# Buck_CurrentRegulator.net
KiCad netlist of a schematic drawn in Altium Designer
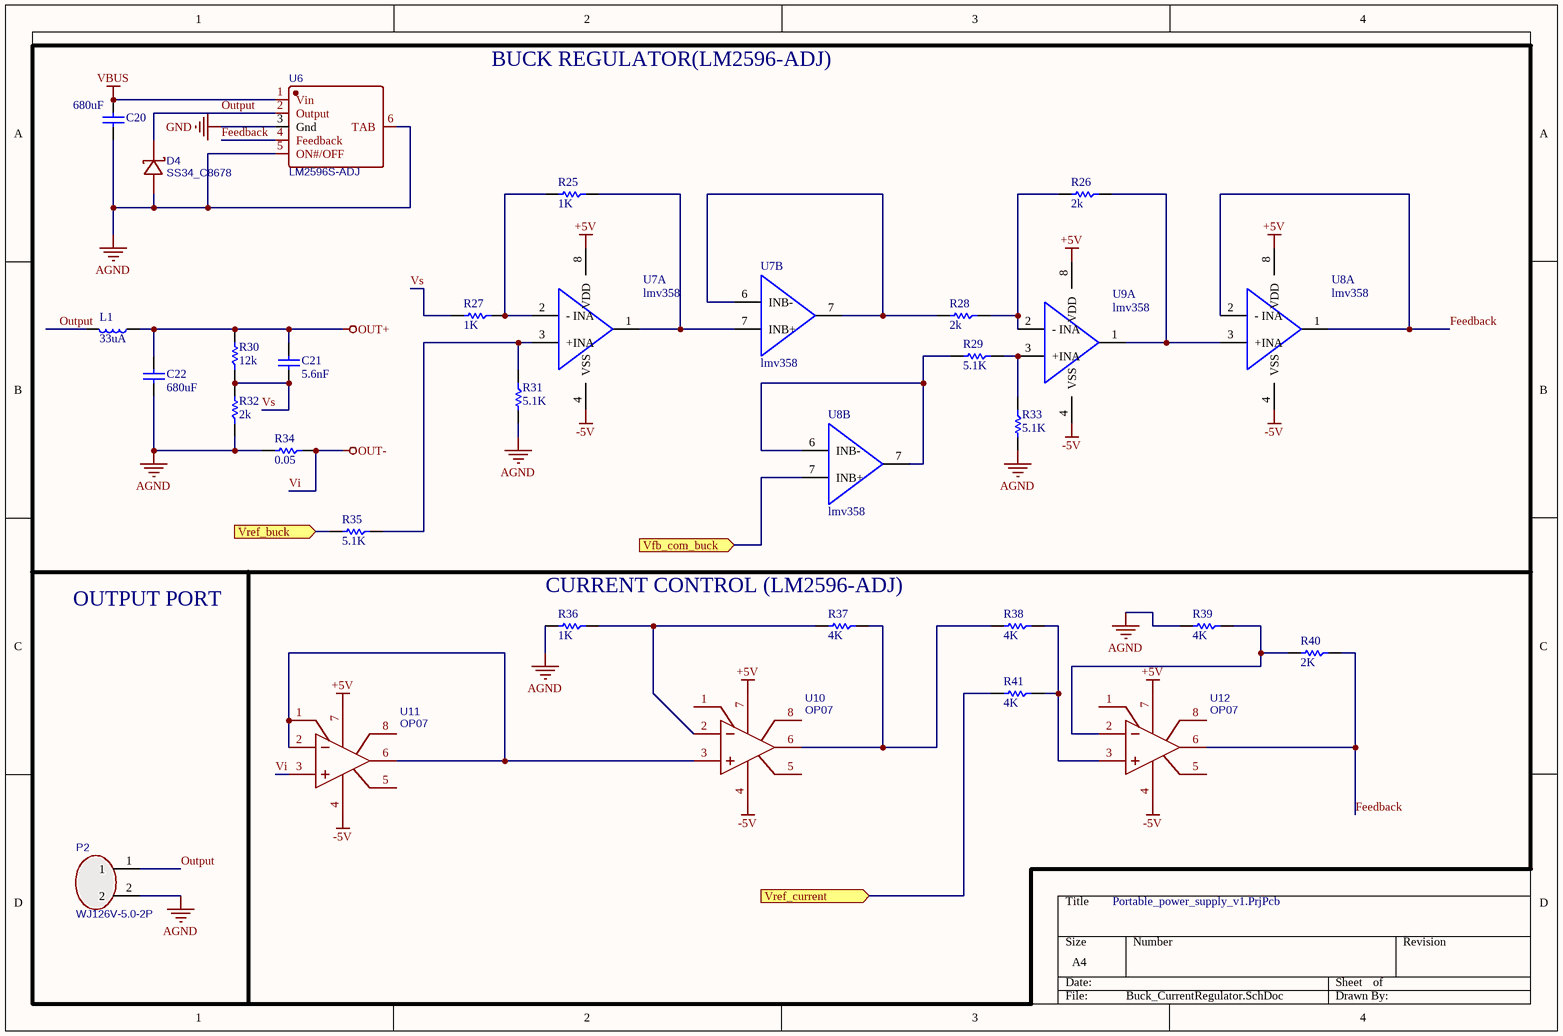
[diagram p0: Buck_CurrentRegulator.SchDoc]

(export (version "E")
  (design (tool "Eeschema 10.0.6"))
  (components
    (comp (ref "C20")
      (value "680uF")
      (footprint "0805C")
      (description "Capacitor")
      (fields (field (name "REVIEWED BY") "RM - 2018/08/05"))
      (libsource (lib "Portable power supply") (part "C_680uf"))
    )
    (comp (ref "C21")
      (value "5.6nF")
      (footprint "0805C")
      (description "Capacitor")
      (fields (field (name "REVIEWED BY") "RM - 2018/08/05"))
      (libsource (lib "Portable power supply") (part "C_7"))
    )
    (comp (ref "C22")
      (value "680uF")
      (footprint "0805C")
      (description "Capacitor")
      (fields (field (name "REVIEWED BY") "RM - 2018/08/05"))
      (libsource (lib "Portable power supply") (part "C_11"))
    )
    (comp (ref "D4")
      (value "SS34_C8678")
      (footprint "DO-214AC_L4.3-W2.7-LS5.3-RD")
      (fields (field (name "BOM_MANUFACTURER PART") "SS34") (field (name "BOM_SUPPLIER PART") "C8678"))
      (libsource (lib "Portable power supply") (part "SS34_C8678"))
    )
    (comp (ref "L1")
      (value "33uA")
      (footprint "0805")
      (description "Inductor")
      (fields (field (name "REVIEWED BY") "RM - 2018/08/05"))
      (libsource (lib "Portable power supply") (part "I"))
    )
    (comp (ref "P2")
      (value "WJ126V-5.0-2P")
      (footprint "CONN-TH_WJ126V-5.0-2P")
      (fields (field (name "BOM_SUPPLIER PART") "C8404"))
      (libsource (lib "Portable power supply") (part "WJ126V-5.0-2P"))
    )
    (comp (ref "R25")
      (value "1K")
      (footprint "0805")
      (description "Resistor")
      (fields (field (name "REVIEWED BY") "RM - 2018/08/05"))
      (libsource (lib "Portable power supply") (part "R_6"))
    )
    (comp (ref "R26")
      (value "2k")
      (footprint "0805")
      (description "Resistor")
      (fields (field (name "REVIEWED BY") "RM - 2018/08/05"))
      (libsource (lib "Portable power supply") (part "R_3"))
    )
    (comp (ref "R27")
      (value "1K")
      (footprint "0805")
      (description "Resistor")
      (fields (field (name "REVIEWED BY") "RM - 2018/08/05"))
      (libsource (lib "Portable power supply") (part "R_6"))
    )
    (comp (ref "R28")
      (value "2k")
      (footprint "0805")
      (description "Resistor")
      (fields (field (name "REVIEWED BY") "RM - 2018/08/05"))
      (libsource (lib "Portable power supply") (part "R_3"))
    )
    (comp (ref "R29")
      (value "5.1K")
      (footprint "0805")
      (description "Resistor")
      (fields (field (name "REVIEWED BY") "RM - 2018/08/05"))
      (libsource (lib "Portable power supply") (part "R_1"))
    )
    (comp (ref "R30")
      (value "12k")
      (footprint "0805")
      (description "Resistor")
      (fields (field (name "REVIEWED BY") "RM - 2018/08/05"))
      (libsource (lib "Portable power supply") (part "R_2"))
    )
    (comp (ref "R31")
      (value "5.1K")
      (footprint "0805")
      (description "Resistor")
      (fields (field (name "REVIEWED BY") "RM - 2018/08/05"))
      (libsource (lib "Portable power supply") (part "R_1"))
    )
    (comp (ref "R32")
      (value "2k")
      (footprint "0805")
      (description "Resistor")
      (fields (field (name "REVIEWED BY") "RM - 2018/08/05"))
      (libsource (lib "Portable power supply") (part "R_3"))
    )
    (comp (ref "R33")
      (value "5.1K")
      (footprint "0805")
      (description "Resistor")
      (fields (field (name "REVIEWED BY") "RM - 2018/08/05"))
      (libsource (lib "Portable power supply") (part "R_1"))
    )
    (comp (ref "R34")
      (value "0.05")
      (footprint "0805")
      (description "Resistor")
      (fields (field (name "REVIEWED BY") "RM - 2018/08/05"))
      (libsource (lib "Portable power supply") (part "R_6"))
    )
    (comp (ref "R35")
      (value "5.1K")
      (footprint "0805")
      (description "Resistor")
      (fields (field (name "REVIEWED BY") "RM - 2018/08/05"))
      (libsource (lib "Portable power supply") (part "R_1"))
    )
    (comp (ref "R36")
      (value "1K")
      (footprint "0805")
      (description "Resistor")
      (fields (field (name "REVIEWED BY") "RM - 2018/08/05"))
      (libsource (lib "power supply ztc") (part "R_1k"))
    )
    (comp (ref "R37")
      (value "4K")
      (footprint "0805")
      (description "Resistor")
      (fields (field (name "REVIEWED BY") "RM - 2018/08/05"))
      (libsource (lib "power supply ztc") (part "R_1k"))
    )
    (comp (ref "R38")
      (value "4K")
      (footprint "0805")
      (description "Resistor")
      (fields (field (name "REVIEWED BY") "RM - 2018/08/05"))
      (libsource (lib "power supply ztc") (part "R_1k"))
    )
    (comp (ref "R39")
      (value "4K")
      (footprint "0805")
      (description "Resistor")
      (fields (field (name "REVIEWED BY") "RM - 2018/08/05"))
      (libsource (lib "power supply ztc") (part "R_1k"))
    )
    (comp (ref "R40")
      (value "2K")
      (footprint "0805")
      (description "Resistor")
      (fields (field (name "REVIEWED BY") "RM - 2018/08/05"))
      (libsource (lib "power supply ztc") (part "R_1k"))
    )
    (comp (ref "R41")
      (value "4K")
      (footprint "0805")
      (description "Resistor")
      (fields (field (name "REVIEWED BY") "RM - 2018/08/05"))
      (libsource (lib "power supply ztc") (part "R_1k"))
    )
    (comp (ref "U6")
      (value "LM2596S-ADJ")
      (footprint "TO-263-5_L10.2-W8.9-P1.70-BR")
      (fields (field (name "BOM_SUPPLIER PART") "C347423") (field (name "CONTRIBUTOR") "LCSC"))
      (libsource (lib "Portable power supply") (part "LM2596S-ADJ"))
    )
    (comp (ref "U7")
      (value "lmv358")
      (footprint "SOP-8_L4.9-W3.9-P1.27-LS6.0-BL")
      (description "OpAmp High Frequency Dual")
      (fields (field (name "REVIEWED BY") "RM - 2018/08/05"))
      (libsource (lib "Portable power supply") (part "LMV358-SR"))
    )
    (comp (ref "U8")
      (value "lmv358")
      (footprint "SOP-8_L4.9-W3.9-P1.27-LS6.0-BL")
      (description "OpAmp High Frequency Dual")
      (fields (field (name "REVIEWED BY") "RM - 2018/08/05"))
      (libsource (lib "Portable power supply") (part "LMV358-SR"))
    )
    (comp (ref "U9")
      (value "lmv358")
      (footprint "SOP-8_L4.9-W3.9-P1.27-LS6.0-BL")
      (description "OpAmp High Frequency Dual")
      (fields (field (name "REVIEWED BY") "RM - 2018/08/05"))
      (libsource (lib "Portable power supply") (part "LMV358-SR"))
    )
    (comp (ref "U10")
      (value "OP07")
      (footprint "op07:SOP-8_L4.9-W3.9-P1.27-LS6.0-BL")
      (fields (field (name "BOM_SUPPLIER PART") "C1508997") (field (name "CONTRIBUTOR") "LCSC"))
      (libsource (lib "op07") (part "OP07"))
    )
    (comp (ref "U11")
      (value "OP07")
      (footprint "op07:SOP-8_L4.9-W3.9-P1.27-LS6.0-BL")
      (fields (field (name "BOM_SUPPLIER PART") "C1508997") (field (name "CONTRIBUTOR") "LCSC"))
      (libsource (lib "op07") (part "OP07"))
    )
    (comp (ref "U12")
      (value "OP07")
      (footprint "op07:SOP-8_L4.9-W3.9-P1.27-LS6.0-BL")
      (fields (field (name "BOM_SUPPLIER PART") "C1508997") (field (name "CONTRIBUTOR") "LCSC"))
      (libsource (lib "op07") (part "OP07"))
    )
  )
  (nets
    (net (code "1") (name "+5V") (class "Default")
      (node (ref "U10") (pin "7") (pinfunction "V+_7") (pintype "passive"))
      (node (ref "U11") (pin "7") (pinfunction "V+_7") (pintype "passive"))
      (node (ref "U12") (pin "7") (pinfunction "V+_7") (pintype "passive"))
      (node (ref "U7") (pin "8") (pinfunction "VDD_8") (pintype "passive"))
      (node (ref "U8") (pin "8") (pinfunction "VDD_8") (pintype "passive"))
      (node (ref "U9") (pin "8") (pinfunction "VDD_8") (pintype "passive"))
    )
    (net (code "2") (name "-5V") (class "Default")
      (node (ref "U10") (pin "4") (pinfunction "V-_4") (pintype "passive"))
      (node (ref "U11") (pin "4") (pinfunction "V-_4") (pintype "passive"))
      (node (ref "U12") (pin "4") (pinfunction "V-_4") (pintype "passive"))
      (node (ref "U7") (pin "4") (pinfunction "VSS_4") (pintype "passive"))
      (node (ref "U8") (pin "4") (pinfunction "VSS_4") (pintype "passive"))
      (node (ref "U9") (pin "4") (pinfunction "VSS_4") (pintype "passive"))
    )
    (net (code "3") (name "/Feedback") (class "Default")
      (node (ref "R40") (pin "1") (pintype "passive"))
      (node (ref "U12") (pin "6") (pinfunction "OUT_6") (pintype "passive"))
      (node (ref "U6") (pin "4") (pinfunction "Feedback_4") (pintype "passive"))
      (node (ref "U8") (pin "1") (pinfunction "OUTA_1") (pintype "passive"))
      (node (ref "U8") (pin "2") (pinfunction "-_INA_2") (pintype "passive"))
    )
    (net (code "4") (name "/Output") (class "Default")
      (node (ref "D4") (pin "1") (pinfunction "K_1") (pintype "passive"))
      (node (ref "L1") (pin "2") (pinfunction "2_2") (pintype "passive"))
      (node (ref "P2") (pin "1") (pinfunction "1_1") (pintype "passive"))
      (node (ref "U6") (pin "2") (pinfunction "Output_2") (pintype "passive"))
    )
    (net (code "5") (name "/Vfb_com_buck") (class "Default")
      (node (ref "U8") (pin "7") (pinfunction "INB+_7") (pintype "passive"))
    )
    (net (code "6") (name "/Vref_buck") (class "Default") (node (ref "R35") (pin "2") (pintype "passive")))
    (net (code "7") (name "/Vref_current") (class "Default") (node (ref "R41") (pin "2") (pintype "passive")))
    (net (code "8") (name "/Vs") (class "Default")
      (node (ref "C21") (pin "2") (pinfunction "2_2") (pintype "passive"))
      (node (ref "R27") (pin "2") (pintype "passive"))
      (node (ref "R30") (pin "1") (pintype "passive"))
      (node (ref "R32") (pin "2") (pintype "passive"))
    )
    (net (code "9") (name "AGND") (class "Default")
      (node (ref "C20") (pin "2") (pinfunction "2_2") (pintype "passive"))
      (node (ref "C22") (pin "1") (pinfunction "1_1") (pintype "passive"))
      (node (ref "D4") (pin "2") (pinfunction "A_2") (pintype "passive"))
      (node (ref "P2") (pin "2") (pinfunction "2_2") (pintype "passive"))
      (node (ref "R31") (pin "2") (pintype "passive"))
      (node (ref "R32") (pin "1") (pintype "passive"))
      (node (ref "R33") (pin "2") (pintype "passive"))
      (node (ref "R34") (pin "2") (pintype "passive"))
      (node (ref "R36") (pin "2") (pintype "passive"))
      (node (ref "R39") (pin "2") (pintype "passive"))
      (node (ref "U6") (pin "5") (pinfunction "ON#/OFF_5") (pintype "passive"))
      (node (ref "U6") (pin "6") (pinfunction "TAB_6") (pintype "passive"))
    )
    (net (code "10") (name "GND") (class "Default")
      (node (ref "U6") (pin "3") (pinfunction "Gnd_3") (pintype "passive"))
    )
    (net (code "11") (name "Net-(U7A-+INA)") (class "Default")
      (node (ref "R31") (pin "1") (pintype "passive"))
      (node (ref "R35") (pin "1") (pintype "passive"))
      (node (ref "U7") (pin "3") (pinfunction "+INA_3") (pintype "passive"))
    )
    (net (code "12") (name "Net-(U7A--_INA)") (class "Default")
      (node (ref "R25") (pin "2") (pintype "passive"))
      (node (ref "R27") (pin "1") (pintype "passive"))
      (node (ref "U7") (pin "2") (pinfunction "-_INA_2") (pintype "passive"))
    )
    (net (code "13") (name "Net-(U7A-OUTA)") (class "Default")
      (node (ref "R25") (pin "1") (pintype "passive"))
      (node (ref "U7") (pin "1") (pinfunction "OUTA_1") (pintype "passive"))
      (node (ref "U7") (pin "7") (pinfunction "INB+_7") (pintype "passive"))
    )
    (net (code "14") (name "Net-(U7B-INB-)") (class "Default")
      (node (ref "R28") (pin "2") (pintype "passive"))
      (node (ref "U7") (pin "6") (pinfunction "INB-_6") (pintype "passive"))
      (node (ref "U7") (pin "7") (pinfunction "OUTB_7") (pintype "passive"))
    )
    (net (code "15") (name "Net-(U8A-+INA)") (class "Default")
      (node (ref "R26") (pin "1") (pintype "passive"))
      (node (ref "U8") (pin "3") (pinfunction "+INA_3") (pintype "passive"))
      (node (ref "U9") (pin "1") (pinfunction "OUTA_1") (pintype "passive"))
    )
    (net (code "16") (name "Net-(U8B-INB-)") (class "Default")
      (node (ref "R29") (pin "2") (pintype "passive"))
      (node (ref "U8") (pin "6") (pinfunction "INB-_6") (pintype "passive"))
      (node (ref "U8") (pin "7") (pinfunction "OUTB_7") (pintype "passive"))
    )
    (net (code "17") (name "Net-(U9A-+INA)") (class "Default")
      (node (ref "R29") (pin "1") (pintype "passive"))
      (node (ref "R33") (pin "1") (pintype "passive"))
      (node (ref "U9") (pin "3") (pinfunction "+INA_3") (pintype "passive"))
    )
    (net (code "18") (name "Net-(U9A--_INA)") (class "Default")
      (node (ref "R26") (pin "2") (pintype "passive"))
      (node (ref "R28") (pin "1") (pintype "passive"))
      (node (ref "U9") (pin "2") (pinfunction "-_INA_2") (pintype "passive"))
    )
    (net (code "19") (name "Net-(U10-IN+)") (class "Default")
      (node (ref "U10") (pin "3") (pinfunction "IN+_3") (pintype "passive"))
      (node (ref "U11") (pin "1") (pinfunction "VOS_TRIM_1") (pintype "passive"))
      (node (ref "U11") (pin "2") (pinfunction "IN-_2") (pintype "passive"))
      (node (ref "U11") (pin "6") (pinfunction "OUT_6") (pintype "passive"))
    )
    (net (code "20") (name "Net-(U10-IN-)") (class "Default")
      (node (ref "R36") (pin "1") (pintype "passive"))
      (node (ref "R37") (pin "2") (pintype "passive"))
      (node (ref "U10") (pin "2") (pinfunction "IN-_2") (pintype "passive"))
    )
    (net (code "21") (name "Net-(U10-OUT)") (class "Default")
      (node (ref "R37") (pin "1") (pintype "passive"))
      (node (ref "R38") (pin "2") (pintype "passive"))
      (node (ref "U10") (pin "6") (pinfunction "OUT_6") (pintype "passive"))
    )
    (net (code "22") (name "Net-(U12-IN+)") (class "Default")
      (node (ref "R38") (pin "1") (pintype "passive"))
      (node (ref "R41") (pin "1") (pintype "passive"))
      (node (ref "U12") (pin "3") (pinfunction "IN+_3") (pintype "passive"))
    )
    (net (code "23") (name "Net-(U12-IN-)") (class "Default")
      (node (ref "R39") (pin "1") (pintype "passive"))
      (node (ref "R40") (pin "2") (pintype "passive"))
      (node (ref "U12") (pin "2") (pinfunction "IN-_2") (pintype "passive"))
    )
    (net (code "24") (name "OUT+") (class "Default")
      (node (ref "C21") (pin "1") (pinfunction "1_1") (pintype "passive"))
      (node (ref "C22") (pin "2") (pinfunction "2_2") (pintype "passive"))
      (node (ref "L1") (pin "1") (pinfunction "1_1") (pintype "passive"))
      (node (ref "R30") (pin "2") (pintype "passive"))
    )
    (net (code "25") (name "OUT-") (class "Default")
      (node (ref "R34") (pin "1") (pintype "passive"))
      (node (ref "U11") (pin "3") (pinfunction "IN+_3") (pintype "passive"))
    )
    (net (code "26") (name "VBUS") (class "Default")
      (node (ref "C20") (pin "1") (pinfunction "1_1") (pintype "passive"))
      (node (ref "U6") (pin "1") (pinfunction "Vin_1") (pintype "passive"))
    )
    (net (code "27") (name "unconnected-(U10-NC-Pad5)") (class "Default")
      (node (ref "U10") (pin "5") (pinfunction "NC_5") (pintype "passive"))
    )
    (net (code "28") (name "unconnected-(U10-VOS_TRIM-Pad1)") (class "Default")
      (node (ref "U10") (pin "1") (pinfunction "VOS_TRIM_1") (pintype "passive"))
    )
    (net (code "29") (name "unconnected-(U10-VOS_TRIM-Pad8)") (class "Default")
      (node (ref "U10") (pin "8") (pinfunction "VOS_TRIM_8") (pintype "passive"))
    )
    (net (code "30") (name "unconnected-(U11-NC-Pad5)") (class "Default")
      (node (ref "U11") (pin "5") (pinfunction "NC_5") (pintype "passive"))
    )
    (net (code "31") (name "unconnected-(U11-VOS_TRIM-Pad8)") (class "Default")
      (node (ref "U11") (pin "8") (pinfunction "VOS_TRIM_8") (pintype "passive"))
    )
    (net (code "32") (name "unconnected-(U12-NC-Pad5)") (class "Default")
      (node (ref "U12") (pin "5") (pinfunction "NC_5") (pintype "passive"))
    )
    (net (code "33") (name "unconnected-(U12-VOS_TRIM-Pad1)") (class "Default")
      (node (ref "U12") (pin "1") (pinfunction "VOS_TRIM_1") (pintype "passive"))
    )
    (net (code "34") (name "unconnected-(U12-VOS_TRIM-Pad8)") (class "Default")
      (node (ref "U12") (pin "8") (pinfunction "VOS_TRIM_8") (pintype "passive"))
    )
  )
)
